# TrackLine_Schematic.net
KiCad netlist of a schematic drawn in EAGLE
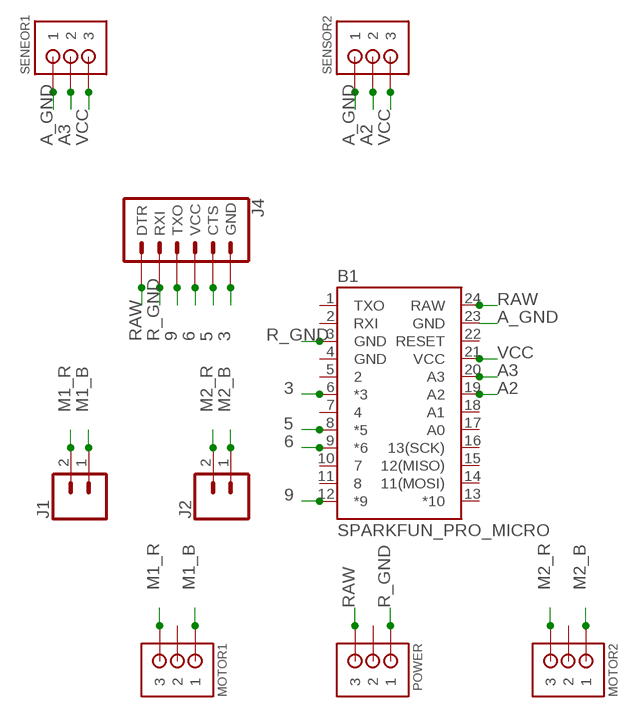
[diagram p0: schematic, sheet 1]

(export (version "E")
  (design (tool "Eeschema 10.0.6"))
  (components
    (comp (ref "B1")
      (value "SPARKFUN_PRO_MICRO")
      (footprint "eagle-import:SPARKFUN_PRO_MICRO")
      (libsource (lib "eagle-import") (part "SPARKFUN_PRO_MICRO"))
    )
    (comp (ref "J1")
      (value "CONN_025MM")
      (footprint "eagle-import:SCREWTERMINAL-5MM-2")
      (libsource (lib "eagle-import") (part "CONN_025MM"))
    )
    (comp (ref "J2")
      (value "CONN_025MM")
      (footprint "eagle-import:SCREWTERMINAL-5MM-2")
      (libsource (lib "eagle-import") (part "CONN_025MM"))
    )
    (comp (ref "J4")
      (value "6_PIN_SERIAL_TARGET")
      (footprint "eagle-import:1X06")
      (libsource (lib "eagle-import") (part "6_PIN_SERIAL_TARGET"))
    )
    (comp (ref "MOTOR1")
      (value "JST-PH_3-PIN_HEADER")
      (footprint "eagle-import:JST_B3B-PH_HEADER")
      (libsource (lib "eagle-import") (part "JST-PH_3-PIN_HEADER"))
    )
    (comp (ref "MOTOR2")
      (value "JST-PH_3-PIN_HEADER")
      (footprint "eagle-import:JST_B3B-PH_HEADER")
      (libsource (lib "eagle-import") (part "JST-PH_3-PIN_HEADER"))
    )
    (comp (ref "POWER")
      (value "JST-PH_3-PIN_HEADER")
      (footprint "eagle-import:JST_B3B-PH_HEADER")
      (libsource (lib "eagle-import") (part "JST-PH_3-PIN_HEADER"))
    )
    (comp (ref "SENEOR1")
      (value "JST-PH_3-PIN_HEADER")
      (footprint "eagle-import:JST_B3B-PH_HEADER")
      (libsource (lib "eagle-import") (part "JST-PH_3-PIN_HEADER"))
    )
    (comp (ref "SENSOR2")
      (value "JST-PH_3-PIN_HEADER")
      (footprint "eagle-import:JST_B3B-PH_HEADER")
      (libsource (lib "eagle-import") (part "JST-PH_3-PIN_HEADER"))
    )
  )
  (nets
    (net (code "1") (name "/3") (class "Default")
      (node (ref "B1") (pin "6") (pinfunction "*3_6") (pintype "bidirectional"))
      (node (ref "J4") (pin "6") (pinfunction "GND_6") (pintype "passive"))
    )
    (net (code "2") (name "/5") (class "Default")
      (node (ref "B1") (pin "8") (pinfunction "*5_8") (pintype "bidirectional"))
      (node (ref "J4") (pin "5") (pinfunction "CTS_5") (pintype "passive"))
    )
    (net (code "3") (name "/6") (class "Default")
      (node (ref "B1") (pin "9") (pinfunction "*6_9") (pintype "bidirectional"))
      (node (ref "J4") (pin "4") (pinfunction "VCC_4") (pintype "passive"))
    )
    (net (code "4") (name "/9") (class "Default")
      (node (ref "B1") (pin "12") (pinfunction "*9_12") (pintype "bidirectional"))
      (node (ref "J4") (pin "3") (pinfunction "TXO_3") (pintype "passive"))
    )
    (net (code "5") (name "/A2") (class "Default")
      (node (ref "B1") (pin "19") (pinfunction "A2_19") (pintype "bidirectional"))
      (node (ref "SENSOR2") (pin "P2") (pinfunction "2_P2") (pintype "bidirectional"))
    )
    (net (code "6") (name "/A3") (class "Default")
      (node (ref "B1") (pin "20") (pinfunction "A3_20") (pintype "bidirectional"))
      (node (ref "SENEOR1") (pin "P2") (pinfunction "2_P2") (pintype "bidirectional"))
    )
    (net (code "7") (name "/A_GND") (class "Default")
      (node (ref "B1") (pin "23") (pinfunction "GND_23") (pintype "power_in"))
      (node (ref "SENEOR1") (pin "P1") (pinfunction "1_P1") (pintype "bidirectional"))
      (node (ref "SENSOR2") (pin "P1") (pinfunction "1_P1") (pintype "bidirectional"))
    )
    (net (code "8") (name "/GND") (class "Default")
      (node (ref "B1") (pin "4") (pinfunction "GND_4") (pintype "power_in"))
    )
    (net (code "9") (name "/M1_B") (class "Default")
      (node (ref "J1") (pin "1") (pinfunction "1_1") (pintype "passive"))
      (node (ref "MOTOR1") (pin "P1") (pinfunction "1_P1") (pintype "bidirectional"))
    )
    (net (code "10") (name "/M1_R") (class "Default")
      (node (ref "J1") (pin "2") (pinfunction "2_2") (pintype "passive"))
      (node (ref "MOTOR1") (pin "P3") (pinfunction "3_P3") (pintype "bidirectional"))
    )
    (net (code "11") (name "/M2_B") (class "Default")
      (node (ref "J2") (pin "1") (pinfunction "1_1") (pintype "passive"))
      (node (ref "MOTOR2") (pin "P1") (pinfunction "1_P1") (pintype "bidirectional"))
    )
    (net (code "12") (name "/M2_R") (class "Default")
      (node (ref "J2") (pin "2") (pinfunction "2_2") (pintype "passive"))
      (node (ref "MOTOR2") (pin "P3") (pinfunction "3_P3") (pintype "bidirectional"))
    )
    (net (code "13") (name "/RAW") (class "Default")
      (node (ref "B1") (pin "24") (pinfunction "RAW_24") (pintype "power_in"))
      (node (ref "J4") (pin "1") (pinfunction "DTR_1") (pintype "passive"))
      (node (ref "POWER") (pin "P3") (pinfunction "3_P3") (pintype "bidirectional"))
    )
    (net (code "14") (name "/R_GND") (class "Default")
      (node (ref "B1") (pin "3") (pinfunction "GND_3") (pintype "power_in"))
      (node (ref "J4") (pin "2") (pinfunction "RXI_2") (pintype "passive"))
      (node (ref "POWER") (pin "P1") (pinfunction "1_P1") (pintype "bidirectional"))
    )
    (net (code "15") (name "/VCC") (class "Default")
      (node (ref "B1") (pin "21") (pinfunction "VCC_21") (pintype "power_in"))
      (node (ref "SENEOR1") (pin "P3") (pinfunction "3_P3") (pintype "bidirectional"))
      (node (ref "SENSOR2") (pin "P3") (pinfunction "3_P3") (pintype "bidirectional"))
    )
    (net (code "16") (name "unconnected-(B1-*10-Pad13)") (class "Default")
      (node (ref "B1") (pin "13") (pinfunction "*10_13") (pintype "bidirectional"))
    )
    (net (code "17") (name "unconnected-(B1-2-Pad5)") (class "Default")
      (node (ref "B1") (pin "5") (pinfunction "2_5") (pintype "bidirectional"))
    )
    (net (code "18") (name "unconnected-(B1-4-Pad7)") (class "Default")
      (node (ref "B1") (pin "7") (pinfunction "4_7") (pintype "bidirectional"))
    )
    (net (code "19") (name "unconnected-(B1-7-Pad10)") (class "Default")
      (node (ref "B1") (pin "10") (pinfunction "7_10") (pintype "bidirectional"))
    )
    (net (code "20") (name "unconnected-(B1-8-Pad11)") (class "Default")
      (node (ref "B1") (pin "11") (pinfunction "8_11") (pintype "bidirectional"))
    )
    (net (code "21") (name "unconnected-(B1-11(MOSI)-Pad14)") (class "Default")
      (node (ref "B1") (pin "14") (pinfunction "11(MOSI)_14") (pintype "bidirectional"))
    )
    (net (code "22") (name "unconnected-(B1-12(MISO)-Pad15)") (class "Default")
      (node (ref "B1") (pin "15") (pinfunction "12(MISO)_15") (pintype "bidirectional"))
    )
    (net (code "23") (name "unconnected-(B1-13(SCK)-Pad16)") (class "Default")
      (node (ref "B1") (pin "16") (pinfunction "13(SCK)_16") (pintype "bidirectional"))
    )
    (net (code "24") (name "unconnected-(B1-A0-Pad17)") (class "Default")
      (node (ref "B1") (pin "17") (pinfunction "A0_17") (pintype "bidirectional"))
    )
    (net (code "25") (name "unconnected-(B1-A1-Pad18)") (class "Default")
      (node (ref "B1") (pin "18") (pinfunction "A1_18") (pintype "bidirectional"))
    )
    (net (code "26") (name "unconnected-(B1-RESET-Pad22)") (class "Default")
      (node (ref "B1") (pin "22") (pinfunction "RESET_22") (pintype "bidirectional"))
    )
    (net (code "27") (name "unconnected-(B1-RXI-Pad2)") (class "Default")
      (node (ref "B1") (pin "2") (pinfunction "RXI_2") (pintype "bidirectional"))
    )
    (net (code "28") (name "unconnected-(B1-TXO-Pad1)") (class "Default")
      (node (ref "B1") (pin "1") (pinfunction "TXO_1") (pintype "bidirectional"))
    )
    (net (code "29") (name "unconnected-(MOTOR1-2-PadP2)") (class "Default")
      (node (ref "MOTOR1") (pin "P2") (pinfunction "2_P2") (pintype "bidirectional"))
    )
    (net (code "30") (name "unconnected-(MOTOR2-2-PadP2)") (class "Default")
      (node (ref "MOTOR2") (pin "P2") (pinfunction "2_P2") (pintype "bidirectional"))
    )
    (net (code "31") (name "unconnected-(POWER-2-PadP2)") (class "Default")
      (node (ref "POWER") (pin "P2") (pinfunction "2_P2") (pintype "bidirectional"))
    )
  )
)
